# AirSensor.net
KiCad netlist of a schematic drawn in EAGLE
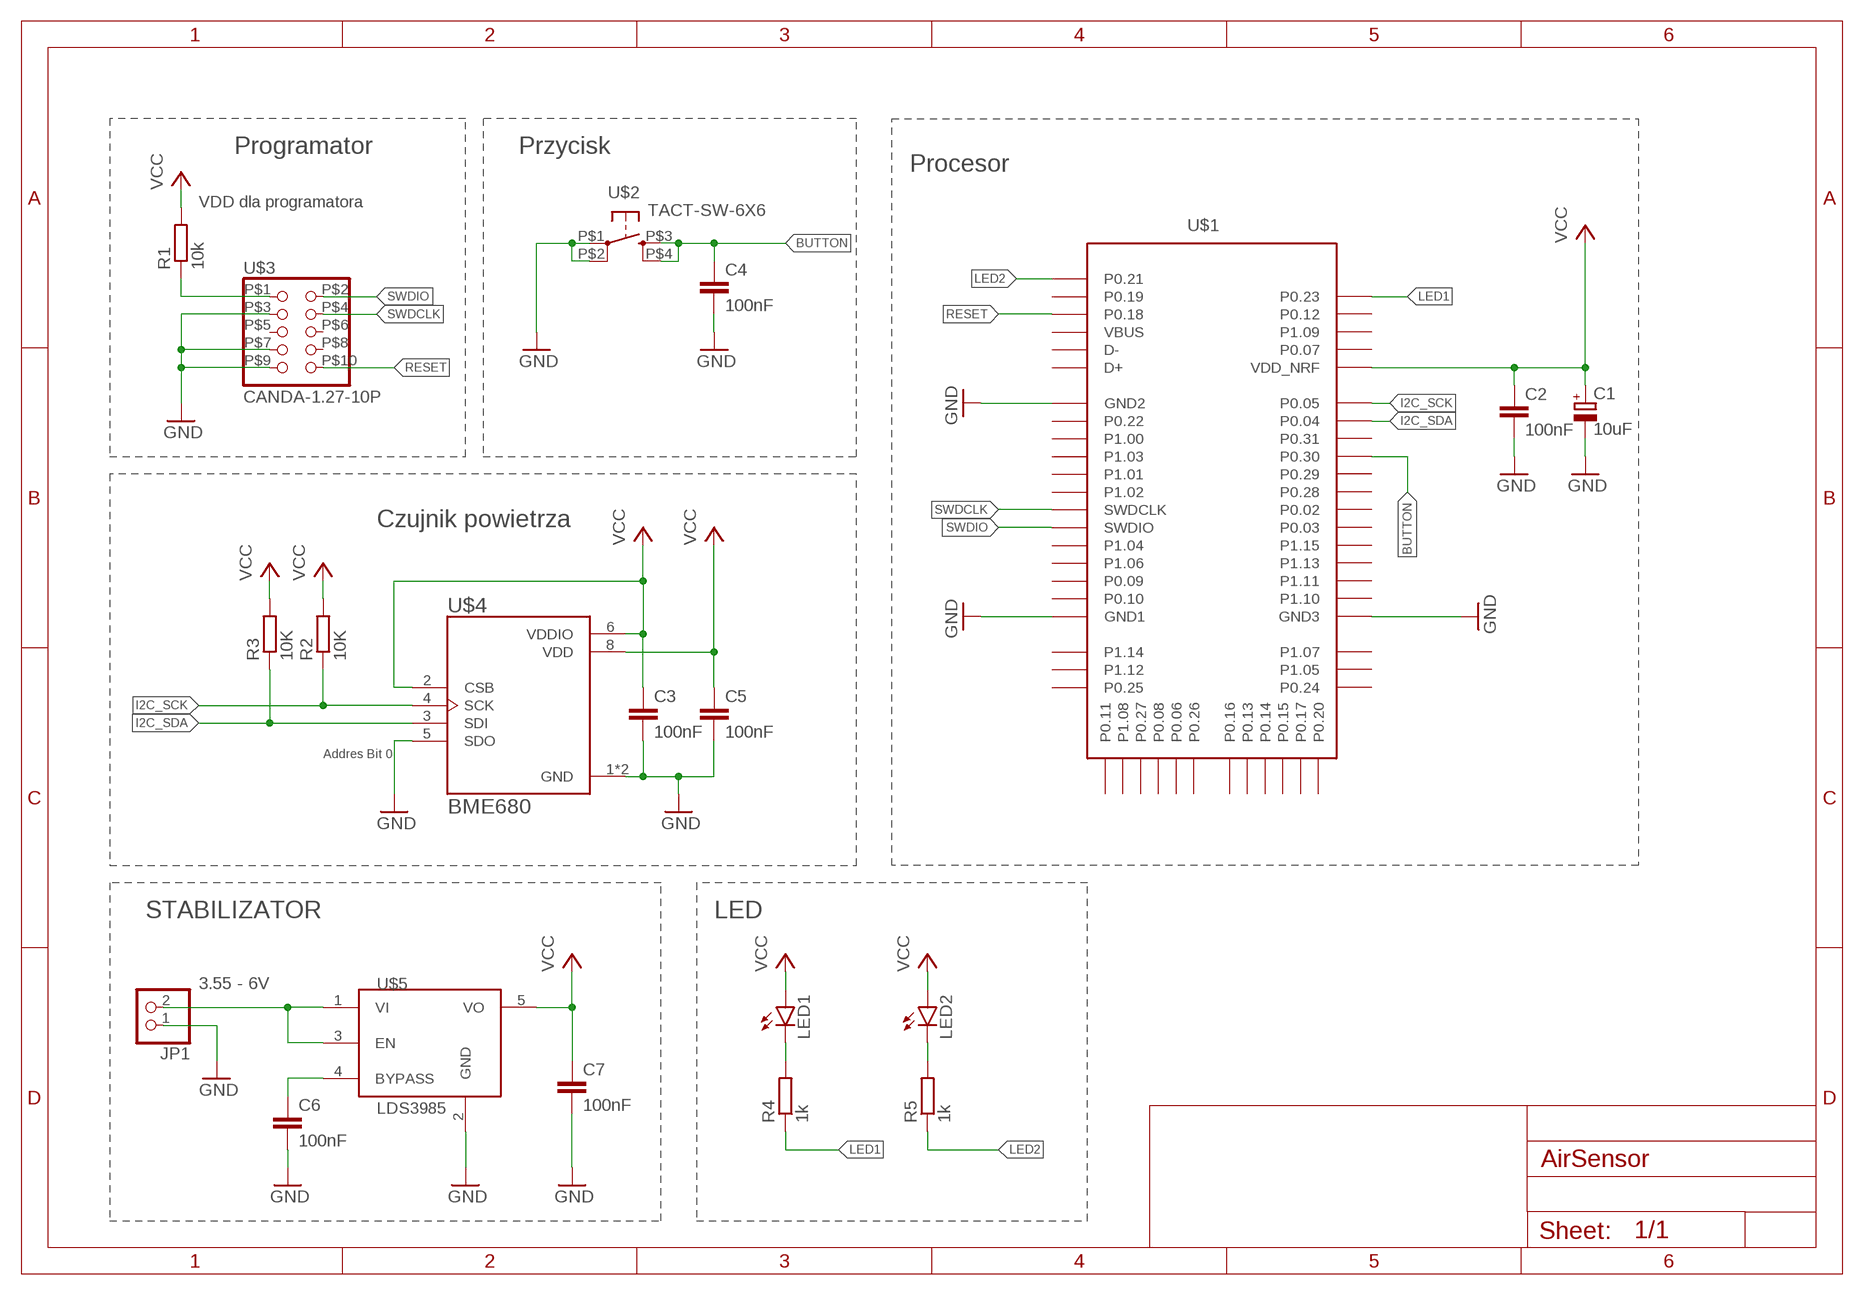
[diagram p0: schematic, sheet 1]

(export (version "E")
  (design (tool "Eeschema 10.0.6"))
  (components
    (comp (ref "C1")
      (value "10uF")
      (footprint "eagle-import:CT6032")
      (libsource (lib "eagle-import") (part "CPOL-EUCT6032"))
    )
    (comp (ref "C2")
      (value "100nF")
      (footprint "eagle-import:C0805K")
      (libsource (lib "eagle-import") (part "C-EUC0805K"))
    )
    (comp (ref "C3")
      (value "100nF")
      (footprint "eagle-import:C0805K")
      (libsource (lib "eagle-import") (part "C-EUC0805K"))
    )
    (comp (ref "C4")
      (value "100nF")
      (footprint "eagle-import:C0805K")
      (libsource (lib "eagle-import") (part "C-EUC0805K"))
    )
    (comp (ref "C5")
      (value "100nF")
      (footprint "eagle-import:C0805K")
      (libsource (lib "eagle-import") (part "C-EUC0805K"))
    )
    (comp (ref "C6")
      (value "100nF")
      (footprint "eagle-import:C0805K")
      (libsource (lib "eagle-import") (part "C-EUC0805K"))
    )
    (comp (ref "C7")
      (value "100nF")
      (footprint "eagle-import:C0805K")
      (libsource (lib "eagle-import") (part "C-EUC0805K"))
    )
    (comp (ref "JP1")
      (value "PINHD-1X2")
      (footprint "eagle-import:1X02")
      (libsource (lib "eagle-import") (part "PINHD-1X2"))
    )
    (comp (ref "LED1")
      (value "LEDCHIPLED_0603")
      (footprint "eagle-import:CHIPLED_0603")
      (libsource (lib "eagle-import") (part "LEDCHIPLED_0603"))
    )
    (comp (ref "LED2")
      (value "LEDCHIPLED_0603")
      (footprint "eagle-import:CHIPLED_0603")
      (libsource (lib "eagle-import") (part "LEDCHIPLED_0603"))
    )
    (comp (ref "R1")
      (value "10k")
      (footprint "eagle-import:R0603")
      (libsource (lib "eagle-import") (part "R-EU_R0603"))
    )
    (comp (ref "R2")
      (value "10K")
      (footprint "eagle-import:R0603")
      (libsource (lib "eagle-import") (part "R-EU_R0603"))
    )
    (comp (ref "R3")
      (value "10K")
      (footprint "eagle-import:R0603")
      (libsource (lib "eagle-import") (part "R-EU_R0603"))
    )
    (comp (ref "R4")
      (value "1k")
      (footprint "eagle-import:R0603")
      (libsource (lib "eagle-import") (part "R-EU_R0603"))
    )
    (comp (ref "R5")
      (value "1k")
      (footprint "eagle-import:R0603")
      (libsource (lib "eagle-import") (part "R-EU_R0603"))
    )
    (comp (ref "U$1")
      (value "HOLYIOT_18010")
      (footprint "eagle-import:PCBCOMPONENT_1")
      (libsource (lib "eagle-import") (part "HOLYIOT_18010"))
    )
    (comp (ref "U$2")
      (value "TACT-SW-6X6")
      (footprint "eagle-import:6X6-TACT-SWITCH-SMD")
      (libsource (lib "eagle-import") (part "TACT-SW-6X6"))
    )
    (comp (ref "U$3")
      (value "CANDA-1.27-10P")
      (footprint "eagle-import:CON-1.27-CANDA")
      (libsource (lib "eagle-import") (part "CANDA-1.27-10P"))
    )
    (comp (ref "U$4")
      (value "BME680")
      (footprint "eagle-import:PSON80P300X300X100-8N")
      (fields (field (name "MF") "Bosch Sensortec"))
      (libsource (lib "eagle-import") (part "BME680"))
    )
    (comp (ref "U$5")
      (value "LDS3985")
      (footprint "eagle-import:SOT23-5")
      (libsource (lib "eagle-import") (part "LDS3985"))
    )
  )
  (nets
    (net (code "1") (name "BUTTON") (class "Default")
      (node (ref "C4") (pin "1") (pinfunction "1_1") (pintype "passive"))
      (node (ref "U$1") (pin "P0.30") (pinfunction "P0.30_P0.30") (pintype "bidirectional"))
      (node (ref "U$2") (pin "P$3") (pinfunction "S_P$3") (pintype "passive"))
      (node (ref "U$2") (pin "P$4") (pinfunction "S1_P$4") (pintype "passive"))
    )
    (net (code "2") (name "GND") (class "Default")
      (node (ref "C1") (pin "-") (pinfunction "-_-") (pintype "passive"))
      (node (ref "C2") (pin "2") (pinfunction "2_2") (pintype "passive"))
      (node (ref "C3") (pin "2") (pinfunction "2_2") (pintype "passive"))
      (node (ref "C4") (pin "2") (pinfunction "2_2") (pintype "passive"))
      (node (ref "C5") (pin "2") (pinfunction "2_2") (pintype "passive"))
      (node (ref "C6") (pin "2") (pinfunction "2_2") (pintype "passive"))
      (node (ref "C7") (pin "2") (pinfunction "2_2") (pintype "passive"))
      (node (ref "JP1") (pin "1") (pinfunction "1_1") (pintype "passive"))
      (node (ref "U$1") (pin "GND") (pinfunction "GND1_GND") (pintype "bidirectional"))
      (node (ref "U$1") (pin "GND1") (pinfunction "GND2_GND1") (pintype "bidirectional"))
      (node (ref "U$1") (pin "GND2") (pinfunction "GND3_GND2") (pintype "bidirectional"))
      (node (ref "U$2") (pin "P$1") (pinfunction "P_P$1") (pintype "passive"))
      (node (ref "U$2") (pin "P$2") (pinfunction "P1_P$2") (pintype "passive"))
      (node (ref "U$3") (pin "P$3") (pinfunction "3_P$3") (pintype "passive"))
      (node (ref "U$3") (pin "P$7") (pinfunction "7_P$7") (pintype "passive"))
      (node (ref "U$3") (pin "P$9") (pinfunction "9_P$9") (pintype "passive"))
      (node (ref "U$4") (pin "1") (pinfunction "GND_1") (pintype "power_in"))
      (node (ref "U$4") (pin "5") (pinfunction "SDO_5") (pintype "bidirectional"))
      (node (ref "U$4") (pin "7") (pinfunction "GND_7") (pintype "power_in"))
      (node (ref "U$5") (pin "2") (pinfunction "GND_2") (pintype "power_in"))
    )
    (net (code "3") (name "I2C_SCK") (class "Default")
      (node (ref "R2") (pin "1") (pinfunction "1_1") (pintype "passive"))
      (node (ref "U$1") (pin "P0.05") (pinfunction "P0.05_P0.05") (pintype "bidirectional"))
      (node (ref "U$4") (pin "4") (pinfunction "SCK_4") (pintype "input"))
    )
    (net (code "4") (name "I2C_SDA") (class "Default")
      (node (ref "R3") (pin "1") (pinfunction "1_1") (pintype "passive"))
      (node (ref "U$1") (pin "P0.04") (pinfunction "P0.04_P0.04") (pintype "bidirectional"))
      (node (ref "U$4") (pin "3") (pinfunction "SDI_3") (pintype "bidirectional"))
    )
    (net (code "5") (name "LED1") (class "Default")
      (node (ref "R4") (pin "1") (pinfunction "1_1") (pintype "passive"))
      (node (ref "U$1") (pin "P0.23") (pinfunction "P0.23_P0.23") (pintype "bidirectional"))
    )
    (net (code "6") (name "LED2") (class "Default")
      (node (ref "R5") (pin "1") (pinfunction "1_1") (pintype "passive"))
      (node (ref "U$1") (pin "P0.21") (pinfunction "P0.21_P0.21") (pintype "bidirectional"))
    )
    (net (code "7") (name "Net-(LED1-PadC)") (class "Default")
      (node (ref "LED1") (pin "C") (pinfunction "C_C") (pintype "passive"))
      (node (ref "R4") (pin "2") (pinfunction "2_2") (pintype "passive"))
    )
    (net (code "8") (name "Net-(LED2-PadC)") (class "Default")
      (node (ref "LED2") (pin "C") (pinfunction "C_C") (pintype "passive"))
      (node (ref "R5") (pin "2") (pinfunction "2_2") (pintype "passive"))
    )
    (net (code "9") (name "Net-(U$3-1)") (class "Default")
      (node (ref "R1") (pin "1") (pinfunction "1_1") (pintype "passive"))
      (node (ref "U$3") (pin "P$1") (pinfunction "1_P$1") (pintype "passive"))
    )
    (net (code "10") (name "Net-(U$5-BYPASS)") (class "Default")
      (node (ref "C6") (pin "1") (pinfunction "1_1") (pintype "passive"))
      (node (ref "U$5") (pin "4") (pinfunction "BYPASS_4") (pintype "bidirectional"))
    )
    (net (code "11") (name "Net-(U$5-EN)") (class "Default")
      (node (ref "JP1") (pin "2") (pinfunction "2_2") (pintype "passive"))
      (node (ref "U$5") (pin "1") (pinfunction "VI_1") (pintype "input"))
      (node (ref "U$5") (pin "3") (pinfunction "EN_3") (pintype "input"))
    )
    (net (code "12") (name "RESET") (class "Default")
      (node (ref "U$1") (pin "P0.18") (pinfunction "P0.18_P0.18") (pintype "bidirectional"))
      (node (ref "U$3") (pin "P$10") (pinfunction "10_P$10") (pintype "passive"))
    )
    (net (code "13") (name "SWDCLK") (class "Default")
      (node (ref "U$1") (pin "SWDCLK") (pinfunction "SWDCLK_SWDCLK") (pintype "bidirectional"))
      (node (ref "U$3") (pin "P$4") (pinfunction "4_P$4") (pintype "passive"))
    )
    (net (code "14") (name "SWDIO") (class "Default")
      (node (ref "U$1") (pin "SWDIO") (pinfunction "SWDIO_SWDIO") (pintype "bidirectional"))
      (node (ref "U$3") (pin "P$2") (pinfunction "2_P$2") (pintype "passive"))
    )
    (net (code "15") (name "VCC") (class "Default")
      (node (ref "C1") (pin "+") (pinfunction "+_+") (pintype "passive"))
      (node (ref "C2") (pin "1") (pinfunction "1_1") (pintype "passive"))
      (node (ref "C3") (pin "1") (pinfunction "1_1") (pintype "passive"))
      (node (ref "C5") (pin "1") (pinfunction "1_1") (pintype "passive"))
      (node (ref "C7") (pin "1") (pinfunction "1_1") (pintype "passive"))
      (node (ref "LED1") (pin "A") (pinfunction "A_A") (pintype "passive"))
      (node (ref "LED2") (pin "A") (pinfunction "A_A") (pintype "passive"))
      (node (ref "R1") (pin "2") (pinfunction "2_2") (pintype "passive"))
      (node (ref "R2") (pin "2") (pinfunction "2_2") (pintype "passive"))
      (node (ref "R3") (pin "2") (pinfunction "2_2") (pintype "passive"))
      (node (ref "U$1") (pin "VDD_NRF") (pinfunction "VDD_NRF_VDD_NRF") (pintype "bidirectional"))
      (node (ref "U$4") (pin "2") (pinfunction "CSB_2") (pintype "input"))
      (node (ref "U$4") (pin "6") (pinfunction "VDDIO_6") (pintype "power_in"))
      (node (ref "U$4") (pin "8") (pinfunction "VDD_8") (pintype "power_in"))
      (node (ref "U$5") (pin "5") (pinfunction "VO_5") (pintype "power_in"))
    )
    (net (code "16") (name "unconnected-(U$1-PadD+)") (class "Default")
      (node (ref "U$1") (pin "D+") (pinfunction "D+_D+") (pintype "bidirectional"))
    )
    (net (code "17") (name "unconnected-(U$1-PadD-)") (class "Default")
      (node (ref "U$1") (pin "D-") (pinfunction "D-_D-") (pintype "bidirectional"))
    )
    (net (code "18") (name "unconnected-(U$1-PadP0.02)") (class "Default")
      (node (ref "U$1") (pin "P0.02") (pinfunction "P0.02_P0.02") (pintype "bidirectional"))
    )
    (net (code "19") (name "unconnected-(U$1-PadP0.03)") (class "Default")
      (node (ref "U$1") (pin "P0.03") (pinfunction "P0.03_P0.03") (pintype "bidirectional"))
    )
    (net (code "20") (name "unconnected-(U$1-PadP0.06)") (class "Default")
      (node (ref "U$1") (pin "P0.06") (pinfunction "P0.06_P0.06") (pintype "bidirectional"))
    )
    (net (code "21") (name "unconnected-(U$1-PadP0.07)") (class "Default")
      (node (ref "U$1") (pin "P0.07") (pinfunction "P0.07_P0.07") (pintype "bidirectional"))
    )
    (net (code "22") (name "unconnected-(U$1-PadP0.08)") (class "Default")
      (node (ref "U$1") (pin "P0.08") (pinfunction "P0.08_P0.08") (pintype "bidirectional"))
    )
    (net (code "23") (name "unconnected-(U$1-PadP0.09)") (class "Default")
      (node (ref "U$1") (pin "P0.09") (pinfunction "P0.09_P0.09") (pintype "bidirectional"))
    )
    (net (code "24") (name "unconnected-(U$1-PadP0.10)") (class "Default")
      (node (ref "U$1") (pin "P0.10") (pinfunction "P0.10_P0.10") (pintype "bidirectional"))
    )
    (net (code "25") (name "unconnected-(U$1-PadP0.11)") (class "Default")
      (node (ref "U$1") (pin "P0.11") (pinfunction "P0.11_P0.11") (pintype "bidirectional"))
    )
    (net (code "26") (name "unconnected-(U$1-PadP0.12)") (class "Default")
      (node (ref "U$1") (pin "P0.12") (pinfunction "P0.12_P0.12") (pintype "bidirectional"))
    )
    (net (code "27") (name "unconnected-(U$1-PadP0.13)") (class "Default")
      (node (ref "U$1") (pin "P0.13") (pinfunction "P0.13_P0.13") (pintype "bidirectional"))
    )
    (net (code "28") (name "unconnected-(U$1-PadP0.14)") (class "Default")
      (node (ref "U$1") (pin "P0.14") (pinfunction "P0.14_P0.14") (pintype "bidirectional"))
    )
    (net (code "29") (name "unconnected-(U$1-PadP0.15)") (class "Default")
      (node (ref "U$1") (pin "P0.15") (pinfunction "P0.15_P0.15") (pintype "bidirectional"))
    )
    (net (code "30") (name "unconnected-(U$1-PadP0.16)") (class "Default")
      (node (ref "U$1") (pin "P0.16") (pinfunction "P0.16_P0.16") (pintype "bidirectional"))
    )
    (net (code "31") (name "unconnected-(U$1-PadP0.17)") (class "Default")
      (node (ref "U$1") (pin "P0.17") (pinfunction "P0.17_P0.17") (pintype "bidirectional"))
    )
    (net (code "32") (name "unconnected-(U$1-PadP0.19)") (class "Default")
      (node (ref "U$1") (pin "P0.19") (pinfunction "P0.19_P0.19") (pintype "bidirectional"))
    )
    (net (code "33") (name "unconnected-(U$1-PadP0.20)") (class "Default")
      (node (ref "U$1") (pin "P0.20") (pinfunction "P0.20_P0.20") (pintype "bidirectional"))
    )
    (net (code "34") (name "unconnected-(U$1-PadP0.22)") (class "Default")
      (node (ref "U$1") (pin "P0.22") (pinfunction "P0.22_P0.22") (pintype "bidirectional"))
    )
    (net (code "35") (name "unconnected-(U$1-PadP0.24)") (class "Default")
      (node (ref "U$1") (pin "P0.24") (pinfunction "P0.24_P0.24") (pintype "bidirectional"))
    )
    (net (code "36") (name "unconnected-(U$1-PadP0.25)") (class "Default")
      (node (ref "U$1") (pin "P0.25") (pinfunction "P0.25_P0.25") (pintype "bidirectional"))
    )
    (net (code "37") (name "unconnected-(U$1-PadP0.26)") (class "Default")
      (node (ref "U$1") (pin "P0.26") (pinfunction "P0.26_P0.26") (pintype "bidirectional"))
    )
    (net (code "38") (name "unconnected-(U$1-PadP0.27)") (class "Default")
      (node (ref "U$1") (pin "P0.27") (pinfunction "P0.27_P0.27") (pintype "bidirectional"))
    )
    (net (code "39") (name "unconnected-(U$1-PadP0.28)") (class "Default")
      (node (ref "U$1") (pin "P0.28") (pinfunction "P0.28_P0.28") (pintype "bidirectional"))
    )
    (net (code "40") (name "unconnected-(U$1-PadP0.29)") (class "Default")
      (node (ref "U$1") (pin "P0.29") (pinfunction "P0.29_P0.29") (pintype "bidirectional"))
    )
    (net (code "41") (name "unconnected-(U$1-PadP0.31)") (class "Default")
      (node (ref "U$1") (pin "P0.31") (pinfunction "P0.31_P0.31") (pintype "bidirectional"))
    )
    (net (code "42") (name "unconnected-(U$1-PadP1.00)") (class "Default")
      (node (ref "U$1") (pin "P1.00") (pinfunction "P1.00_P1.00") (pintype "bidirectional"))
    )
    (net (code "43") (name "unconnected-(U$1-PadP1.01)") (class "Default")
      (node (ref "U$1") (pin "P1.01") (pinfunction "P1.01_P1.01") (pintype "bidirectional"))
    )
    (net (code "44") (name "unconnected-(U$1-PadP1.02)") (class "Default")
      (node (ref "U$1") (pin "P1.02") (pinfunction "P1.02_P1.02") (pintype "bidirectional"))
    )
    (net (code "45") (name "unconnected-(U$1-PadP1.03)") (class "Default")
      (node (ref "U$1") (pin "P1.03") (pinfunction "P1.03_P1.03") (pintype "bidirectional"))
    )
    (net (code "46") (name "unconnected-(U$1-PadP1.04)") (class "Default")
      (node (ref "U$1") (pin "P1.04") (pinfunction "P1.04_P1.04") (pintype "bidirectional"))
    )
    (net (code "47") (name "unconnected-(U$1-PadP1.05)") (class "Default")
      (node (ref "U$1") (pin "P1.05") (pinfunction "P1.05_P1.05") (pintype "bidirectional"))
    )
    (net (code "48") (name "unconnected-(U$1-PadP1.06)") (class "Default")
      (node (ref "U$1") (pin "P1.06") (pinfunction "P1.06_P1.06") (pintype "bidirectional"))
    )
    (net (code "49") (name "unconnected-(U$1-PadP1.07)") (class "Default")
      (node (ref "U$1") (pin "P1.07") (pinfunction "P1.07_P1.07") (pintype "bidirectional"))
    )
    (net (code "50") (name "unconnected-(U$1-PadP1.08)") (class "Default")
      (node (ref "U$1") (pin "P1.08") (pinfunction "P1.08_P1.08") (pintype "bidirectional"))
    )
    (net (code "51") (name "unconnected-(U$1-PadP1.09)") (class "Default")
      (node (ref "U$1") (pin "P1.09") (pinfunction "P1.09_P1.09") (pintype "bidirectional"))
    )
    (net (code "52") (name "unconnected-(U$1-PadP1.10)") (class "Default")
      (node (ref "U$1") (pin "P1.10") (pinfunction "P1.10_P1.10") (pintype "bidirectional"))
    )
    (net (code "53") (name "unconnected-(U$1-PadP1.11)") (class "Default")
      (node (ref "U$1") (pin "P1.11") (pinfunction "P1.11_P1.11") (pintype "bidirectional"))
    )
    (net (code "54") (name "unconnected-(U$1-PadP1.12)") (class "Default")
      (node (ref "U$1") (pin "P1.12") (pinfunction "P1.12_P1.12") (pintype "bidirectional"))
    )
    (net (code "55") (name "unconnected-(U$1-PadP1.13)") (class "Default")
      (node (ref "U$1") (pin "P1.13") (pinfunction "P1.13_P1.13") (pintype "bidirectional"))
    )
    (net (code "56") (name "unconnected-(U$1-PadP1.14)") (class "Default")
      (node (ref "U$1") (pin "P1.14") (pinfunction "P1.14_P1.14") (pintype "bidirectional"))
    )
    (net (code "57") (name "unconnected-(U$1-PadP1.15)") (class "Default")
      (node (ref "U$1") (pin "P1.15") (pinfunction "P1.15_P1.15") (pintype "bidirectional"))
    )
    (net (code "58") (name "unconnected-(U$1-PadVBUS)") (class "Default")
      (node (ref "U$1") (pin "VBUS") (pinfunction "VBUS_VBUS") (pintype "bidirectional"))
    )
    (net (code "59") (name "unconnected-(U$3-5-PadP$5)") (class "Default")
      (node (ref "U$3") (pin "P$5") (pinfunction "5_P$5") (pintype "passive"))
    )
    (net (code "60") (name "unconnected-(U$3-6-PadP$6)") (class "Default")
      (node (ref "U$3") (pin "P$6") (pinfunction "6_P$6") (pintype "passive"))
    )
    (net (code "61") (name "unconnected-(U$3-8-PadP$8)") (class "Default")
      (node (ref "U$3") (pin "P$8") (pinfunction "8_P$8") (pintype "passive"))
    )
  )
)
